# HG2-B.net
KiCad netlist of a schematic drawn in EAGLE
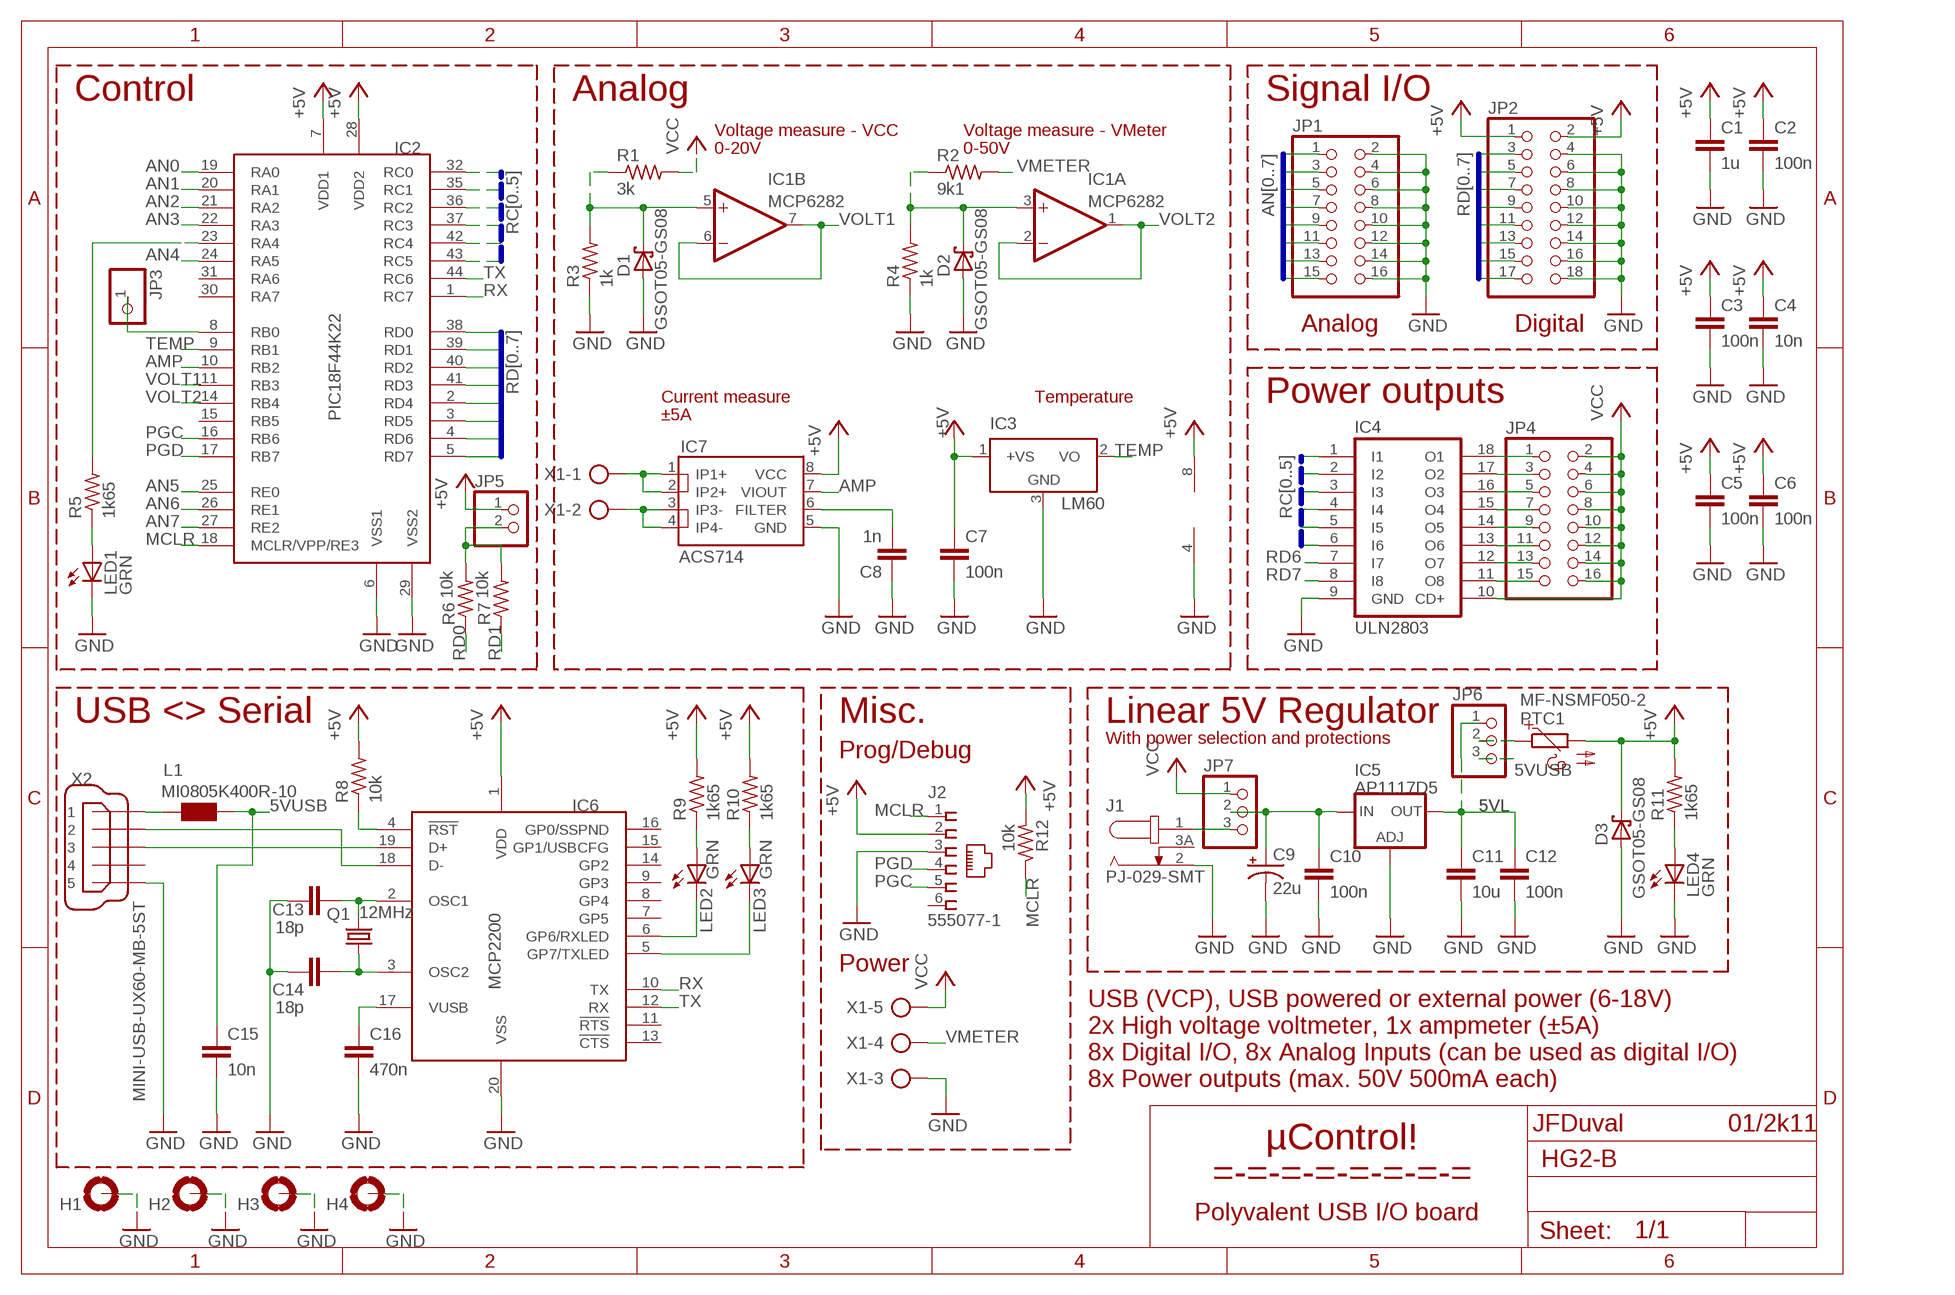
[diagram p0: schematic, sheet 1]

(export (version "E")
  (design (tool "Eeschema 10.0.6"))
  (components
    (comp (ref "C1")
      (value "1u")
      (footprint "eagle-import:C0603")
      (libsource (lib "eagle-import") (part "C-EUC0603"))
    )
    (comp (ref "C2")
      (value "100n")
      (footprint "eagle-import:C0603")
      (libsource (lib "eagle-import") (part "C-EUC0603"))
    )
    (comp (ref "C3")
      (value "100n")
      (footprint "eagle-import:C0603")
      (libsource (lib "eagle-import") (part "C-EUC0603"))
    )
    (comp (ref "C4")
      (value "10n")
      (footprint "eagle-import:C0603")
      (libsource (lib "eagle-import") (part "C-EUC0603"))
    )
    (comp (ref "C5")
      (value "100n")
      (footprint "eagle-import:C0603")
      (libsource (lib "eagle-import") (part "C-EUC0603"))
    )
    (comp (ref "C6")
      (value "100n")
      (footprint "eagle-import:C0603")
      (libsource (lib "eagle-import") (part "C-EUC0603"))
    )
    (comp (ref "C7")
      (value "100n")
      (footprint "eagle-import:C0603")
      (libsource (lib "eagle-import") (part "C-EUC0603"))
    )
    (comp (ref "C8")
      (value "1n")
      (footprint "eagle-import:C0603")
      (libsource (lib "eagle-import") (part "C-EUC0603"))
    )
    (comp (ref "C9")
      (value "22u")
      (footprint "eagle-import:153CLV-0505")
      (libsource (lib "eagle-import") (part "CPOL-US153CLV-0505"))
    )
    (comp (ref "C10")
      (value "100n")
      (footprint "eagle-import:C0603")
      (libsource (lib "eagle-import") (part "C-EUC0603"))
    )
    (comp (ref "C11")
      (value "10u")
      (footprint "eagle-import:C0805")
      (libsource (lib "eagle-import") (part "C-EUC0805"))
    )
    (comp (ref "C12")
      (value "100n")
      (footprint "eagle-import:C0603")
      (libsource (lib "eagle-import") (part "C-EUC0603"))
    )
    (comp (ref "C13")
      (value "18p")
      (footprint "eagle-import:C0603")
      (libsource (lib "eagle-import") (part "C-EUC0603"))
    )
    (comp (ref "C14")
      (value "18p")
      (footprint "eagle-import:C0603")
      (libsource (lib "eagle-import") (part "C-EUC0603"))
    )
    (comp (ref "C15")
      (value "10n")
      (footprint "eagle-import:C0603")
      (libsource (lib "eagle-import") (part "C-EUC0603"))
    )
    (comp (ref "C16")
      (value "470n")
      (footprint "eagle-import:C0603")
      (libsource (lib "eagle-import") (part "C-EUC0603"))
    )
    (comp (ref "D1")
      (value "GSOT05-GS08")
      (footprint "eagle-import:SOT23")
      (libsource (lib "eagle-import") (part "BAS70"))
    )
    (comp (ref "D2")
      (value "GSOT05-GS08")
      (footprint "eagle-import:SOT23")
      (libsource (lib "eagle-import") (part "BAS70"))
    )
    (comp (ref "D3")
      (value "GSOT05-GS08")
      (footprint "eagle-import:SOT23")
      (libsource (lib "eagle-import") (part "BAS70"))
    )
    (comp (ref "H1")
      (value "MOUNT-PAD-ROUND3.2")
      (footprint "eagle-import:3,2-PAD")
      (libsource (lib "eagle-import") (part "MOUNT-PAD-ROUND3.2"))
    )
    (comp (ref "H2")
      (value "MOUNT-PAD-ROUND3.2")
      (footprint "eagle-import:3,2-PAD")
      (libsource (lib "eagle-import") (part "MOUNT-PAD-ROUND3.2"))
    )
    (comp (ref "H3")
      (value "MOUNT-PAD-ROUND3.2")
      (footprint "eagle-import:3,2-PAD")
      (libsource (lib "eagle-import") (part "MOUNT-PAD-ROUND3.2"))
    )
    (comp (ref "H4")
      (value "MOUNT-PAD-ROUND3.2")
      (footprint "eagle-import:3,2-PAD")
      (libsource (lib "eagle-import") (part "MOUNT-PAD-ROUND3.2"))
    )
    (comp (ref "IC1")
      (value "MCP6282")
      (footprint "eagle-import:SO08")
      (libsource (lib "eagle-import") (part "MCP602SN"))
    )
    (comp (ref "IC2")
      (value "PIC18F44K22")
      (footprint "eagle-import:TQFP44")
      (libsource (lib "eagle-import") (part "PIC18F44K22"))
    )
    (comp (ref "IC3")
      (value "LM60")
      (footprint "eagle-import:SOT23")
      (libsource (lib "eagle-import") (part "LM50"))
    )
    (comp (ref "IC4")
      (value "ULN2803")
      (footprint "eagle-import:SO18")
      (libsource (lib "eagle-import") (part "ULN2803"))
    )
    (comp (ref "IC5")
      (value "AP1117D5")
      (footprint "eagle-import:DPACK")
      (libsource (lib "eagle-import") (part "LD117A?DT33TR"))
    )
    (comp (ref "IC6")
      (value "MCP2200")
      (footprint "eagle-import:SSOP20")
      (libsource (lib "eagle-import") (part "MCP2200"))
    )
    (comp (ref "IC7")
      (value "ACS714")
      (footprint "eagle-import:SO08")
      (libsource (lib "eagle-import") (part "ACS712"))
    )
    (comp (ref "J1")
      (value "PJ-029-SMT")
      (footprint "eagle-import:SMT")
      (libsource (lib "eagle-import") (part "PJ-029-SMT"))
    )
    (comp (ref "J2")
      (value "555077-1")
      (footprint "eagle-import:555077-1")
      (libsource (lib "eagle-import") (part "555077-1"))
    )
    (comp (ref "JP1")
      (value "PINHD-2X8")
      (footprint "eagle-import:2X08")
      (libsource (lib "eagle-import") (part "PINHD-2X8"))
    )
    (comp (ref "JP2")
      (value "PINHD-2X9")
      (footprint "eagle-import:2X09")
      (libsource (lib "eagle-import") (part "PINHD-2X9"))
    )
    (comp (ref "JP3")
      (value "PINHD-1X1")
      (footprint "eagle-import:1X01")
      (libsource (lib "eagle-import") (part "PINHD-1X1"))
    )
    (comp (ref "JP4")
      (value "PINHD-2X8")
      (footprint "eagle-import:2X08")
      (libsource (lib "eagle-import") (part "PINHD-2X8"))
    )
    (comp (ref "JP5")
      (value "PINHD-1X2")
      (footprint "eagle-import:1X02")
      (libsource (lib "eagle-import") (part "PINHD-1X2"))
    )
    (comp (ref "JP6")
      (value "PINHD-1X3")
      (footprint "eagle-import:1X03")
      (libsource (lib "eagle-import") (part "PINHD-1X3"))
    )
    (comp (ref "JP7")
      (value "PINHD-1X3")
      (footprint "eagle-import:1X03")
      (libsource (lib "eagle-import") (part "PINHD-1X3"))
    )
    (comp (ref "L1")
      (value "MI0805K400R-10")
      (footprint "eagle-import:0805")
      (libsource (lib "eagle-import") (part "WE-CBF_0805"))
    )
    (comp (ref "LED1")
      (value "GRN")
      (footprint "eagle-import:CHIPLED_0603")
      (libsource (lib "eagle-import") (part "LEDCHIPLED_0603"))
    )
    (comp (ref "LED2")
      (value "GRN")
      (footprint "eagle-import:CHIPLED_0603")
      (libsource (lib "eagle-import") (part "LEDCHIPLED_0603"))
    )
    (comp (ref "LED3")
      (value "GRN")
      (footprint "eagle-import:CHIPLED_0603")
      (libsource (lib "eagle-import") (part "LEDCHIPLED_0603"))
    )
    (comp (ref "LED4")
      (value "GRN")
      (footprint "eagle-import:CHIPLED_0603")
      (libsource (lib "eagle-import") (part "LEDCHIPLED_0603"))
    )
    (comp (ref "PTC1")
      (value "MF-NSMF050-2")
      (footprint "eagle-import:1206")
      (libsource (lib "eagle-import") (part "GENERIC_1206"))
    )
    (comp (ref "Q1")
      (value "12MHz")
      (footprint "eagle-import:HC49UP")
      (libsource (lib "eagle-import") (part "CRYSTALHC49UP"))
    )
    (comp (ref "R1")
      (value "3k")
      (footprint "eagle-import:R0603")
      (libsource (lib "eagle-import") (part "R-US_R0603"))
    )
    (comp (ref "R2")
      (value "9k1")
      (footprint "eagle-import:R0603")
      (libsource (lib "eagle-import") (part "R-US_R0603"))
    )
    (comp (ref "R3")
      (value "1k")
      (footprint "eagle-import:R0603")
      (libsource (lib "eagle-import") (part "R-US_R0603"))
    )
    (comp (ref "R4")
      (value "1k")
      (footprint "eagle-import:R0603")
      (libsource (lib "eagle-import") (part "R-US_R0603"))
    )
    (comp (ref "R5")
      (value "1k65")
      (footprint "eagle-import:R0603")
      (libsource (lib "eagle-import") (part "R-US_R0603"))
    )
    (comp (ref "R6")
      (value "10k")
      (footprint "eagle-import:R0603")
      (libsource (lib "eagle-import") (part "R-US_R0603"))
    )
    (comp (ref "R7")
      (value "10k")
      (footprint "eagle-import:R0603")
      (libsource (lib "eagle-import") (part "R-US_R0603"))
    )
    (comp (ref "R8")
      (value "10k")
      (footprint "eagle-import:R0603")
      (libsource (lib "eagle-import") (part "R-US_R0603"))
    )
    (comp (ref "R9")
      (value "1k65")
      (footprint "eagle-import:R0603")
      (libsource (lib "eagle-import") (part "R-US_R0603"))
    )
    (comp (ref "R10")
      (value "1k65")
      (footprint "eagle-import:R0603")
      (libsource (lib "eagle-import") (part "R-US_R0603"))
    )
    (comp (ref "R11")
      (value "1k65")
      (footprint "eagle-import:R0603")
      (libsource (lib "eagle-import") (part "R-US_R0603"))
    )
    (comp (ref "R12")
      (value "10k")
      (footprint "eagle-import:R0603")
      (libsource (lib "eagle-import") (part "R-US_R0603"))
    )
    (comp (ref "X1")
      (value "OSTTE-5")
      (footprint "eagle-import:OSTTE-5")
      (libsource (lib "eagle-import") (part "OSTTE-5"))
    )
    (comp (ref "X2")
      (value "MINI-USB-UX60-MB-5ST")
      (footprint "eagle-import:UX60-MB-5ST")
      (libsource (lib "eagle-import") (part "MINI-USB-UX60-MB-5ST"))
    )
  )
  (nets
    (net (code "1") (name "+5V") (class "Default")
      (node (ref "C1") (pin "1") (pinfunction "1_1") (pintype "passive"))
      (node (ref "C2") (pin "1") (pinfunction "1_1") (pintype "passive"))
      (node (ref "C3") (pin "1") (pinfunction "1_1") (pintype "passive"))
      (node (ref "C4") (pin "1") (pinfunction "1_1") (pintype "passive"))
      (node (ref "C5") (pin "1") (pinfunction "1_1") (pintype "passive"))
      (node (ref "C6") (pin "1") (pinfunction "1_1") (pintype "passive"))
      (node (ref "C7") (pin "1") (pinfunction "1_1") (pintype "passive"))
      (node (ref "D3") (pin "3") (pinfunction "C_3") (pintype "passive"))
      (node (ref "IC1") (pin "8") (pinfunction "V+_8") (pintype "power_in"))
      (node (ref "IC2") (pin "28") (pinfunction "VDD2_28") (pintype "power_in"))
      (node (ref "IC2") (pin "7") (pinfunction "VDD1_7") (pintype "power_in"))
      (node (ref "IC3") (pin "1") (pinfunction "+VS_1") (pintype "input"))
      (node (ref "IC6") (pin "1") (pinfunction "VDD_1") (pintype "bidirectional"))
      (node (ref "IC7") (pin "8") (pinfunction "VCC_8") (pintype "power_in"))
      (node (ref "J2") (pin "2") (pinfunction "2_2") (pintype "passive"))
      (node (ref "JP2") (pin "1") (pinfunction "1_1") (pintype "passive"))
      (node (ref "JP2") (pin "2") (pinfunction "2_2") (pintype "passive"))
      (node (ref "JP5") (pin "1") (pinfunction "1_1") (pintype "passive"))
      (node (ref "PTC1") (pin "2") (pinfunction "2_2") (pintype "passive"))
      (node (ref "R10") (pin "2") (pinfunction "2_2") (pintype "passive"))
      (node (ref "R11") (pin "2") (pinfunction "2_2") (pintype "passive"))
      (node (ref "R12") (pin "2") (pinfunction "2_2") (pintype "passive"))
      (node (ref "R8") (pin "2") (pinfunction "2_2") (pintype "passive"))
      (node (ref "R9") (pin "2") (pinfunction "2_2") (pintype "passive"))
    )
    (net (code "2") (name "/5VL") (class "Default")
      (node (ref "C11") (pin "1") (pinfunction "1_1") (pintype "passive"))
      (node (ref "C12") (pin "1") (pinfunction "1_1") (pintype "passive"))
      (node (ref "IC5") (pin "4") (pinfunction "OUT_4") (pintype "passive"))
      (node (ref "JP6") (pin "1") (pinfunction "1_1") (pintype "passive"))
    )
    (net (code "3") (name "/5VUSB") (class "Default")
      (node (ref "C15") (pin "1") (pinfunction "1_1") (pintype "passive"))
      (node (ref "JP6") (pin "3") (pinfunction "3_3") (pintype "passive"))
      (node (ref "L1") (pin "1") (pinfunction "1_1") (pintype "passive"))
    )
    (net (code "4") (name "/AMP") (class "Default")
      (node (ref "IC2") (pin "10") (pinfunction "RB2_10") (pintype "bidirectional"))
      (node (ref "IC7") (pin "7") (pinfunction "VIOUT_7") (pintype "output"))
    )
    (net (code "5") (name "/AN0") (class "Default")
      (node (ref "IC2") (pin "19") (pinfunction "RA0_19") (pintype "bidirectional"))
      (node (ref "JP1") (pin "15") (pinfunction "15_15") (pintype "passive"))
    )
    (net (code "6") (name "/AN1") (class "Default")
      (node (ref "IC2") (pin "20") (pinfunction "RA1_20") (pintype "bidirectional"))
      (node (ref "JP1") (pin "13") (pinfunction "13_13") (pintype "passive"))
    )
    (net (code "7") (name "/AN2") (class "Default")
      (node (ref "IC2") (pin "21") (pinfunction "RA2_21") (pintype "bidirectional"))
      (node (ref "JP1") (pin "11") (pinfunction "11_11") (pintype "passive"))
    )
    (net (code "8") (name "/AN3") (class "Default")
      (node (ref "IC2") (pin "22") (pinfunction "RA3_22") (pintype "bidirectional"))
      (node (ref "JP1") (pin "9") (pinfunction "9_9") (pintype "passive"))
    )
    (net (code "9") (name "/AN4") (class "Default")
      (node (ref "IC2") (pin "24") (pinfunction "RA5_24") (pintype "bidirectional"))
      (node (ref "JP1") (pin "7") (pinfunction "7_7") (pintype "passive"))
    )
    (net (code "10") (name "/AN5") (class "Default")
      (node (ref "IC2") (pin "25") (pinfunction "RE0_25") (pintype "bidirectional"))
      (node (ref "JP1") (pin "5") (pinfunction "5_5") (pintype "passive"))
    )
    (net (code "11") (name "/AN6") (class "Default")
      (node (ref "IC2") (pin "26") (pinfunction "RE1_26") (pintype "bidirectional"))
      (node (ref "JP1") (pin "3") (pinfunction "3_3") (pintype "passive"))
    )
    (net (code "12") (name "/AN7") (class "Default")
      (node (ref "IC2") (pin "27") (pinfunction "RE2_27") (pintype "bidirectional"))
      (node (ref "JP1") (pin "1") (pinfunction "1_1") (pintype "passive"))
    )
    (net (code "14") (name "/MCLR") (class "Default")
      (node (ref "IC2") (pin "18") (pinfunction "MCLR/VPP/RE3_18") (pintype "bidirectional"))
      (node (ref "J2") (pin "1") (pinfunction "1_1") (pintype "passive"))
      (node (ref "R12") (pin "1") (pinfunction "1_1") (pintype "passive"))
    )
    (net (code "15") (name "/PGC") (class "Default")
      (node (ref "IC2") (pin "16") (pinfunction "RB6_16") (pintype "bidirectional"))
      (node (ref "J2") (pin "5") (pinfunction "5_5") (pintype "passive"))
    )
    (net (code "16") (name "/PGD") (class "Default")
      (node (ref "IC2") (pin "17") (pinfunction "RB7_17") (pintype "bidirectional"))
      (node (ref "J2") (pin "4") (pinfunction "4_4") (pintype "passive"))
    )
    (net (code "17") (name "/RC0") (class "Default")
      (node (ref "IC2") (pin "32") (pinfunction "RC0_32") (pintype "bidirectional"))
      (node (ref "IC4") (pin "6") (pinfunction "I6_6") (pintype "input"))
    )
    (net (code "18") (name "/RC1") (class "Default")
      (node (ref "IC2") (pin "35") (pinfunction "RC1_35") (pintype "bidirectional"))
      (node (ref "IC4") (pin "5") (pinfunction "I5_5") (pintype "input"))
    )
    (net (code "19") (name "/RC2") (class "Default")
      (node (ref "IC2") (pin "36") (pinfunction "RC2_36") (pintype "bidirectional"))
      (node (ref "IC4") (pin "4") (pinfunction "I4_4") (pintype "input"))
    )
    (net (code "20") (name "/RC3") (class "Default")
      (node (ref "IC2") (pin "37") (pinfunction "RC3_37") (pintype "bidirectional"))
      (node (ref "IC4") (pin "3") (pinfunction "I3_3") (pintype "input"))
    )
    (net (code "21") (name "/RC4") (class "Default")
      (node (ref "IC2") (pin "42") (pinfunction "RC4_42") (pintype "bidirectional"))
      (node (ref "IC4") (pin "2") (pinfunction "I2_2") (pintype "input"))
    )
    (net (code "22") (name "/RC5") (class "Default")
      (node (ref "IC2") (pin "43") (pinfunction "RC5_43") (pintype "bidirectional"))
      (node (ref "IC4") (pin "1") (pinfunction "I1_1") (pintype "input"))
    )
    (net (code "24") (name "/RD0") (class "Default")
      (node (ref "IC2") (pin "38") (pinfunction "RD0_38") (pintype "bidirectional"))
      (node (ref "JP2") (pin "17") (pinfunction "17_17") (pintype "passive"))
      (node (ref "R6") (pin "1") (pinfunction "1_1") (pintype "passive"))
    )
    (net (code "25") (name "/RD1") (class "Default")
      (node (ref "IC2") (pin "39") (pinfunction "RD1_39") (pintype "bidirectional"))
      (node (ref "JP2") (pin "15") (pinfunction "15_15") (pintype "passive"))
      (node (ref "R7") (pin "1") (pinfunction "1_1") (pintype "passive"))
    )
    (net (code "26") (name "/RD2") (class "Default")
      (node (ref "IC2") (pin "40") (pinfunction "RD2_40") (pintype "bidirectional"))
      (node (ref "JP2") (pin "13") (pinfunction "13_13") (pintype "passive"))
    )
    (net (code "27") (name "/RD3") (class "Default")
      (node (ref "IC2") (pin "41") (pinfunction "RD3_41") (pintype "bidirectional"))
      (node (ref "JP2") (pin "11") (pinfunction "11_11") (pintype "passive"))
    )
    (net (code "28") (name "/RD4") (class "Default")
      (node (ref "IC2") (pin "2") (pinfunction "RD4_2") (pintype "bidirectional"))
      (node (ref "JP2") (pin "9") (pinfunction "9_9") (pintype "passive"))
    )
    (net (code "29") (name "/RD5") (class "Default")
      (node (ref "IC2") (pin "3") (pinfunction "RD5_3") (pintype "bidirectional"))
      (node (ref "JP2") (pin "7") (pinfunction "7_7") (pintype "passive"))
    )
    (net (code "30") (name "/RD6") (class "Default")
      (node (ref "IC2") (pin "4") (pinfunction "RD6_4") (pintype "bidirectional"))
      (node (ref "IC4") (pin "7") (pinfunction "I7_7") (pintype "input"))
      (node (ref "JP2") (pin "5") (pinfunction "5_5") (pintype "passive"))
    )
    (net (code "31") (name "/RD7") (class "Default")
      (node (ref "IC2") (pin "5") (pinfunction "RD7_5") (pintype "bidirectional"))
      (node (ref "IC4") (pin "8") (pinfunction "I8_8") (pintype "input"))
      (node (ref "JP2") (pin "3") (pinfunction "3_3") (pintype "passive"))
    )
    (net (code "33") (name "/RX") (class "Default")
      (node (ref "IC2") (pin "1") (pinfunction "RC7_1") (pintype "bidirectional"))
      (node (ref "IC6") (pin "10") (pinfunction "TX_10") (pintype "bidirectional"))
    )
    (net (code "34") (name "/TEMP") (class "Default")
      (node (ref "IC2") (pin "9") (pinfunction "RB1_9") (pintype "bidirectional"))
      (node (ref "IC3") (pin "2") (pinfunction "VO_2") (pintype "input"))
    )
    (net (code "35") (name "/TX") (class "Default")
      (node (ref "IC2") (pin "44") (pinfunction "RC6_44") (pintype "bidirectional"))
      (node (ref "IC6") (pin "12") (pinfunction "RX_12") (pintype "bidirectional"))
    )
    (net (code "36") (name "/VMETER") (class "Default")
      (node (ref "R2") (pin "2") (pinfunction "2_2") (pintype "passive"))
      (node (ref "X1") (pin "4") (pinfunction "KL_4") (pintype "passive"))
    )
    (net (code "37") (name "/VOLT1") (class "Default")
      (node (ref "IC1") (pin "6") (pinfunction "-IN_6") (pintype "input"))
      (node (ref "IC1") (pin "7") (pinfunction "OUT_7") (pintype "output"))
      (node (ref "IC2") (pin "11") (pinfunction "RB3_11") (pintype "bidirectional"))
    )
    (net (code "38") (name "/VOLT2") (class "Default")
      (node (ref "IC1") (pin "1") (pinfunction "OUT_1") (pintype "output"))
      (node (ref "IC1") (pin "2") (pinfunction "-IN_2") (pintype "input"))
      (node (ref "IC2") (pin "14") (pinfunction "RB4_14") (pintype "bidirectional"))
    )
    (net (code "39") (name "GND") (class "Default")
      (node (ref "C1") (pin "2") (pinfunction "2_2") (pintype "passive"))
      (node (ref "C10") (pin "2") (pinfunction "2_2") (pintype "passive"))
      (node (ref "C11") (pin "2") (pinfunction "2_2") (pintype "passive"))
      (node (ref "C12") (pin "2") (pinfunction "2_2") (pintype "passive"))
      (node (ref "C13") (pin "1") (pinfunction "1_1") (pintype "passive"))
      (node (ref "C14") (pin "1") (pinfunction "1_1") (pintype "passive"))
      (node (ref "C15") (pin "2") (pinfunction "2_2") (pintype "passive"))
      (node (ref "C16") (pin "2") (pinfunction "2_2") (pintype "passive"))
      (node (ref "C2") (pin "2") (pinfunction "2_2") (pintype "passive"))
      (node (ref "C3") (pin "2") (pinfunction "2_2") (pintype "passive"))
      (node (ref "C4") (pin "2") (pinfunction "2_2") (pintype "passive"))
      (node (ref "C5") (pin "2") (pinfunction "2_2") (pintype "passive"))
      (node (ref "C6") (pin "2") (pinfunction "2_2") (pintype "passive"))
      (node (ref "C7") (pin "2") (pinfunction "2_2") (pintype "passive"))
      (node (ref "C8") (pin "1") (pinfunction "1_1") (pintype "passive"))
      (node (ref "C9") (pin "-") (pinfunction "-_-") (pintype "passive"))
      (node (ref "D1") (pin "1") (pinfunction "A_1") (pintype "passive"))
      (node (ref "D2") (pin "1") (pinfunction "A_1") (pintype "passive"))
      (node (ref "D3") (pin "1") (pinfunction "A_1") (pintype "passive"))
      (node (ref "H1") (pin "B3,2") (pinfunction "MOUNT_B3,2") (pintype "passive"))
      (node (ref "H2") (pin "B3,2") (pinfunction "MOUNT_B3,2") (pintype "passive"))
      (node (ref "H3") (pin "B3,2") (pinfunction "MOUNT_B3,2") (pintype "passive"))
      (node (ref "H4") (pin "B3,2") (pinfunction "MOUNT_B3,2") (pintype "passive"))
      (node (ref "IC1") (pin "4") (pinfunction "V-_4") (pintype "power_in"))
      (node (ref "IC2") (pin "29") (pinfunction "VSS2_29") (pintype "power_in"))
      (node (ref "IC2") (pin "6") (pinfunction "VSS1_6") (pintype "power_in"))
      (node (ref "IC3") (pin "3") (pinfunction "GND_3") (pintype "power_in"))
      (node (ref "IC4") (pin "9") (pinfunction "GND_9") (pintype "power_in"))
      (node (ref "IC5") (pin "1") (pinfunction "ADJ_1") (pintype "input"))
      (node (ref "IC6") (pin "20") (pinfunction "VSS_20") (pintype "bidirectional"))
      (node (ref "IC7") (pin "5") (pinfunction "GND_5") (pintype "power_in"))
      (node (ref "J1") (pin "2") (pinfunction "1_2") (pintype "passive"))
      (node (ref "J2") (pin "3") (pinfunction "3_3") (pintype "passive"))
      (node (ref "JP1") (pin "10") (pinfunction "10_10") (pintype "passive"))
      (node (ref "JP1") (pin "12") (pinfunction "12_12") (pintype "passive"))
      (node (ref "JP1") (pin "14") (pinfunction "14_14") (pintype "passive"))
      (node (ref "JP1") (pin "16") (pinfunction "16_16") (pintype "passive"))
      (node (ref "JP1") (pin "2") (pinfunction "2_2") (pintype "passive"))
      (node (ref "JP1") (pin "4") (pinfunction "4_4") (pintype "passive"))
      (node (ref "JP1") (pin "6") (pinfunction "6_6") (pintype "passive"))
      (node (ref "JP1") (pin "8") (pinfunction "8_8") (pintype "passive"))
      (node (ref "JP2") (pin "10") (pinfunction "10_10") (pintype "passive"))
      (node (ref "JP2") (pin "12") (pinfunction "12_12") (pintype "passive"))
      (node (ref "JP2") (pin "14") (pinfunction "14_14") (pintype "passive"))
      (node (ref "JP2") (pin "16") (pinfunction "16_16") (pintype "passive"))
      (node (ref "JP2") (pin "18") (pinfunction "18_18") (pintype "passive"))
      (node (ref "JP2") (pin "4") (pinfunction "4_4") (pintype "passive"))
      (node (ref "JP2") (pin "6") (pinfunction "6_6") (pintype "passive"))
      (node (ref "JP2") (pin "8") (pinfunction "8_8") (pintype "passive"))
      (node (ref "LED1") (pin "C") (pinfunction "C_C") (pintype "passive"))
      (node (ref "LED4") (pin "C") (pinfunction "C_C") (pintype "passive"))
      (node (ref "R3") (pin "1") (pinfunction "1_1") (pintype "passive"))
      (node (ref "R4") (pin "1") (pinfunction "1_1") (pintype "passive"))
      (node (ref "X1") (pin "3") (pinfunction "KL_3") (pintype "passive"))
      (node (ref "X2") (pin "5") (pinfunction "5_5") (pintype "input"))
    )
    (net (code "40") (name "Net-(D1-C)") (class "Default")
      (node (ref "D1") (pin "3") (pinfunction "C_3") (pintype "passive"))
      (node (ref "IC1") (pin "5") (pinfunction "+IN_5") (pintype "input"))
      (node (ref "R1") (pin "1") (pinfunction "1_1") (pintype "passive"))
      (node (ref "R3") (pin "2") (pinfunction "2_2") (pintype "passive"))
    )
    (net (code "41") (name "Net-(D2-C)") (class "Default")
      (node (ref "D2") (pin "3") (pinfunction "C_3") (pintype "passive"))
      (node (ref "IC1") (pin "3") (pinfunction "+IN_3") (pintype "input"))
      (node (ref "R2") (pin "1") (pinfunction "1_1") (pintype "passive"))
      (node (ref "R4") (pin "2") (pinfunction "2_2") (pintype "passive"))
    )
    (net (code "42") (name "Net-(IC2-RA4)") (class "Default")
      (node (ref "IC2") (pin "23") (pinfunction "RA4_23") (pintype "bidirectional"))
      (node (ref "R5") (pin "2") (pinfunction "2_2") (pintype "passive"))
    )
    (net (code "43") (name "Net-(IC2-RB0)") (class "Default")
      (node (ref "IC2") (pin "8") (pinfunction "RB0_8") (pintype "bidirectional"))
      (node (ref "JP3") (pin "1") (pinfunction "1_1") (pintype "passive"))
    )
    (net (code "44") (name "Net-(IC4-O1)") (class "Default")
      (node (ref "IC4") (pin "18") (pinfunction "O1_18") (pintype "open_collector"))
      (node (ref "JP4") (pin "1") (pinfunction "1_1") (pintype "passive"))
    )
    (net (code "45") (name "Net-(IC4-O2)") (class "Default")
      (node (ref "IC4") (pin "17") (pinfunction "O2_17") (pintype "open_collector"))
      (node (ref "JP4") (pin "3") (pinfunction "3_3") (pintype "passive"))
    )
    (net (code "46") (name "Net-(IC4-O3)") (class "Default")
      (node (ref "IC4") (pin "16") (pinfunction "O3_16") (pintype "open_collector"))
      (node (ref "JP4") (pin "5") (pinfunction "5_5") (pintype "passive"))
    )
    (net (code "47") (name "Net-(IC4-O4)") (class "Default")
      (node (ref "IC4") (pin "15") (pinfunction "O4_15") (pintype "open_collector"))
      (node (ref "JP4") (pin "7") (pinfunction "7_7") (pintype "passive"))
    )
    (net (code "48") (name "Net-(IC4-O5)") (class "Default")
      (node (ref "IC4") (pin "14") (pinfunction "O5_14") (pintype "open_collector"))
      (node (ref "JP4") (pin "9") (pinfunction "9_9") (pintype "passive"))
    )
    (net (code "49") (name "Net-(IC4-O6)") (class "Default")
      (node (ref "IC4") (pin "13") (pinfunction "O6_13") (pintype "open_collector"))
      (node (ref "JP4") (pin "11") (pinfunction "11_11") (pintype "passive"))
    )
    (net (code "50") (name "Net-(IC4-O7)") (class "Default")
      (node (ref "IC4") (pin "12") (pinfunction "O7_12") (pintype "open_collector"))
      (node (ref "JP4") (pin "13") (pinfunction "13_13") (pintype "passive"))
    )
    (net (code "51") (name "Net-(IC4-O8)") (class "Default")
      (node (ref "IC4") (pin "11") (pinfunction "O8_11") (pintype "open_collector"))
      (node (ref "JP4") (pin "15") (pinfunction "15_15") (pintype "passive"))
    )
    (net (code "52") (name "Net-(IC5-IN)") (class "Default")
      (node (ref "C10") (pin "1") (pinfunction "1_1") (pintype "passive"))
      (node (ref "C9") (pin "+") (pinfunction "+_+") (pintype "passive"))
      (node (ref "IC5") (pin "3") (pinfunction "IN_3") (pintype "input"))
      (node (ref "JP7") (pin "2") (pinfunction "2_2") (pintype "passive"))
    )
    (net (code "53") (name "Net-(IC6-D+)") (class "Default")
      (node (ref "IC6") (pin "19") (pinfunction "D+_19") (pintype "bidirectional"))
      (node (ref "X2") (pin "3") (pinfunction "3_3") (pintype "input"))
    )
    (net (code "54") (name "Net-(IC6-D-)") (class "Default")
      (node (ref "IC6") (pin "18") (pinfunction "D-_18") (pintype "bidirectional"))
      (node (ref "X2") (pin "2") (pinfunction "2_2") (pintype "input"))
    )
    (net (code "55") (name "Net-(IC6-GP6{slash}RXLED)") (class "Default")
      (node (ref "IC6") (pin "6") (pinfunction "GP6/RXLED_6") (pintype "bidirectional"))
      (node (ref "LED2") (pin "C") (pinfunction "C_C") (pintype "passive"))
    )
    (net (code "56") (name "Net-(IC6-GP7{slash}TXLED)") (class "Default")
      (node (ref "IC6") (pin "5") (pinfunction "GP7/TXLED_5") (pintype "bidirectional"))
      (node (ref "LED3") (pin "C") (pinfunction "C_C") (pintype "passive"))
    )
    (net (code "57") (name "Net-(IC6-OSC1)") (class "Default")
      (node (ref "C13") (pin "2") (pinfunction "2_2") (pintype "passive"))
      (node (ref "IC6") (pin "2") (pinfunction "OSC1_2") (pintype "bidirectional"))
      (node (ref "Q1") (pin "2") (pinfunction "2_2") (pintype "passive"))
    )
    (net (code "58") (name "Net-(IC6-OSC2)") (class "Default")
      (node (ref "C14") (pin "2") (pinfunction "2_2") (pintype "passive"))
      (node (ref "IC6") (pin "3") (pinfunction "OSC2_3") (pintype "bidirectional"))
      (node (ref "Q1") (pin "1") (pinfunction "1_1") (pintype "passive"))
    )
    (net (code "59") (name "Net-(IC6-VUSB)") (class "Default")
      (node (ref "C16") (pin "1") (pinfunction "1_1") (pintype "passive"))
      (node (ref "IC6") (pin "17") (pinfunction "VUSB_17") (pintype "bidirectional"))
    )
    (net (code "60") (name "Net-(IC6-~{RST})") (class "Default")
      (node (ref "IC6") (pin "4") (pinfunction "~{RST}_4") (pintype "bidirectional"))
      (node (ref "R8") (pin "1") (pinfunction "1_1") (pintype "passive"))
    )
    (net (code "61") (name "Net-(IC7-FILTER)") (class "Default")
      (node (ref "C8") (pin "2") (pinfunction "2_2") (pintype "passive"))
      (node (ref "IC7") (pin "6") (pinfunction "FILTER_6") (pintype "passive"))
    )
    (net (code "62") (name "Net-(IC7-IP1+)") (class "Default")
      (node (ref "IC7") (pin "1") (pinfunction "IP1+_1") (pintype "bidirectional"))
      (node (ref "IC7") (pin "2") (pinfunction "IP2+_2") (pintype "bidirectional"))
      (node (ref "X1") (pin "1") (pinfunction "KL_1") (pintype "passive"))
    )
    (net (code "63") (name "Net-(IC7-IP3-)") (class "Default")
      (node (ref "IC7") (pin "3") (pinfunction "IP3-_3") (pintype "bidirectional"))
      (node (ref "IC7") (pin "4") (pinfunction "IP4-_4") (pintype "bidirectional"))
      (node (ref "X1") (pin "2") (pinfunction "KL_2") (pintype "passive"))
    )
    (net (code "64") (name "Net-(J1-3)") (class "Default")
      (node (ref "J1") (pin "1") (pinfunction "3_1") (pintype "passive"))
      (node (ref "JP7") (pin "3") (pinfunction "3_3") (pintype "passive"))
    )
    (net (code "65") (name "Net-(JP5-Pad2)") (class "Default")
      (node (ref "JP5") (pin "2") (pinfunction "2_2") (pintype "passive"))
      (node (ref "R6") (pin "2") (pinfunction "2_2") (pintype "passive"))
      (node (ref "R7") (pin "2") (pinfunction "2_2") (pintype "passive"))
    )
    (net (code "66") (name "Net-(JP6-Pad2)") (class "Default")
      (node (ref "JP6") (pin "2") (pinfunction "2_2") (pintype "passive"))
      (node (ref "PTC1") (pin "1") (pinfunction "1_1") (pintype "passive"))
    )
    (net (code "67") (name "Net-(L1-Pad2)") (class "Default")
      (node (ref "L1") (pin "2") (pinfunction "2_2") (pintype "passive"))
      (node (ref "X2") (pin "1") (pinfunction "1_1") (pintype "input"))
    )
    (net (code "68") (name "Net-(LED1-PadA)") (class "Default")
      (node (ref "LED1") (pin "A") (pinfunction "A_A") (pintype "passive"))
      (node (ref "R5") (pin "1") (pinfunction "1_1") (pintype "passive"))
    )
    (net (code "69") (name "Net-(LED2-PadA)") (class "Default")
      (node (ref "LED2") (pin "A") (pinfunction "A_A") (pintype "passive"))
      (node (ref "R9") (pin "1") (pinfunction "1_1") (pintype "passive"))
    )
    (net (code "70") (name "Net-(LED3-PadA)") (class "Default")
      (node (ref "LED3") (pin "A") (pinfunction "A_A") (pintype "passive"))
      (node (ref "R10") (pin "1") (pinfunction "1_1") (pintype "passive"))
    )
    (net (code "71") (name "Net-(LED4-PadA)") (class "Default")
      (node (ref "LED4") (pin "A") (pinfunction "A_A") (pintype "passive"))
      (node (ref "R11") (pin "1") (pinfunction "1_1") (pintype "passive"))
    )
    (net (code "72") (name "VCC") (class "Default")
      (node (ref "IC4") (pin "10") (pinfunction "CD+_10") (pintype "passive"))
      (node (ref "JP4") (pin "10") (pinfunction "10_10") (pintype "passive"))
      (node (ref "JP4") (pin "12") (pinfunction "12_12") (pintype "passive"))
      (node (ref "JP4") (pin "14") (pinfunction "14_14") (pintype "passive"))
      (node (ref "JP4") (pin "16") (pinfunction "16_16") (pintype "passive"))
      (node (ref "JP4") (pin "2") (pinfunction "2_2") (pintype "passive"))
      (node (ref "JP4") (pin "4") (pinfunction "4_4") (pintype "passive"))
      (node (ref "JP4") (pin "6") (pinfunction "6_6") (pintype "passive"))
      (node (ref "JP4") (pin "8") (pinfunction "8_8") (pintype "passive"))
      (node (ref "JP7") (pin "1") (pinfunction "1_1") (pintype "passive"))
      (node (ref "R1") (pin "2") (pinfunction "2_2") (pintype "passive"))
      (node (ref "X1") (pin "5") (pinfunction "KL_5") (pintype "passive"))
    )
    (net (code "73") (name "unconnected-(IC2-RA6-Pad31)") (class "Default")
      (node (ref "IC2") (pin "31") (pinfunction "RA6_31") (pintype "bidirectional"))
    )
    (net (code "74") (name "unconnected-(IC2-RA7-Pad30)") (class "Default")
      (node (ref "IC2") (pin "30") (pinfunction "RA7_30") (pintype "bidirectional"))
    )
    (net (code "75") (name "unconnected-(IC2-RB5-Pad15)") (class "Default")
      (node (ref "IC2") (pin "15") (pinfunction "RB5_15") (pintype "bidirectional"))
    )
    (net (code "76") (name "unconnected-(IC6-GP0{slash}SSPND-Pad16)") (class "Default")
      (node (ref "IC6") (pin "16") (pinfunction "GP0/SSPND_16") (pintype "bidirectional"))
    )
    (net (code "77") (name "unconnected-(IC6-GP1{slash}USBCFG-Pad15)") (class "Default")
      (node (ref "IC6") (pin "15") (pinfunction "GP1/USBCFG_15") (pintype "bidirectional"))
    )
    (net (code "78") (name "unconnected-(IC6-GP2-Pad14)") (class "Default")
      (node (ref "IC6") (pin "14") (pinfunction "GP2_14") (pintype "bidirectional"))
    )
    (net (code "79") (name "unconnected-(IC6-GP3-Pad9)") (class "Default")
      (node (ref "IC6") (pin "9") (pinfunction "GP3_9") (pintype "bidirectional"))
    )
    (net (code "80") (name "unconnected-(IC6-GP4-Pad8)") (class "Default")
      (node (ref "IC6") (pin "8") (pinfunction "GP4_8") (pintype "bidirectional"))
    )
    (net (code "81") (name "unconnected-(IC6-GP5-Pad7)") (class "Default")
      (node (ref "IC6") (pin "7") (pinfunction "GP5_7") (pintype "bidirectional"))
    )
    (net (code "82") (name "unconnected-(IC6-~{CTS}-Pad13)") (class "Default")
      (node (ref "IC6") (pin "13") (pinfunction "~{CTS}_13") (pintype "bidirectional"))
    )
    (net (code "83") (name "unconnected-(IC6-~{RTS}-Pad11)") (class "Default")
      (node (ref "IC6") (pin "11") (pinfunction "~{RTS}_11") (pintype "bidirectional"))
    )
    (net (code "84") (name "unconnected-(J1-2-Pad3A)") (class "Default")
      (node (ref "J1") (pin "3A") (pinfunction "2_3A") (pintype "passive"))
    )
    (net (code "85") (name "unconnected-(J2-Pad6)") (class "Default")
      (node (ref "J2") (pin "6") (pinfunction "6_6") (pintype "passive"))
    )
    (net (code "86") (name "unconnected-(X2-Pad4)") (class "Default")
      (node (ref "X2") (pin "4") (pinfunction "4_4") (pintype "input"))
    )
  )
)
